# Lcd3_5Connect.net
KiCad netlist of a schematic drawn in EAGLE
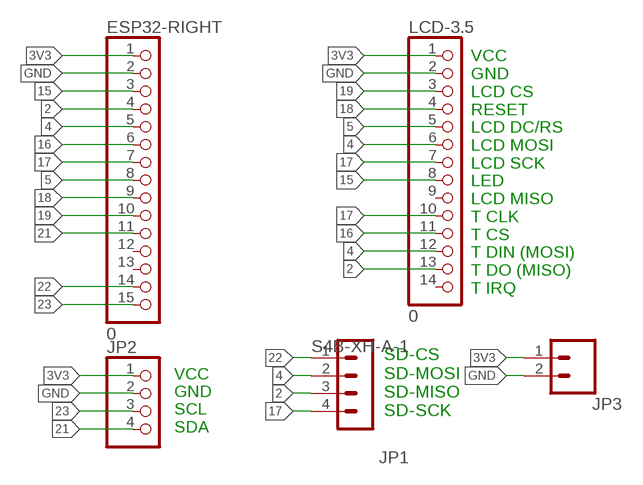
[diagram p0: schematic, sheet 1]

(export (version "E")
  (design (tool "Eeschema 10.0.6"))
  (components
    (comp (ref "ESP32-RIGHT")
      (value "0")
      (footprint "eagle-import:1X15")
      (libsource (lib "eagle-import") (part "PINHD-1X15"))
    )
    (comp (ref "JP1")
      (value "S4B-XH-A-1")
      (footprint "eagle-import:S4B-XH-A-1")
      (libsource (lib "eagle-import") (part "S4B-XH-A-1"))
    )
    (comp (ref "JP2")
      (value "PINHD-1X4")
      (footprint "eagle-import:1X04")
      (libsource (lib "eagle-import") (part "PINHD-1X4"))
    )
    (comp (ref "JP3")
      (value "CONN_02")
      (footprint "eagle-import:1X02")
      (libsource (lib "eagle-import") (part "CONN_02"))
    )
    (comp (ref "LCD-3.5")
      (value "0")
      (footprint "eagle-import:1X14")
      (libsource (lib "eagle-import") (part "PINHD-1X14"))
    )
  )
  (nets
    (net (code "1") (name "2") (class "Default")
      (node (ref "ESP32-RIGHT") (pin "4") (pinfunction "4_4") (pintype "passive"))
      (node (ref "JP1") (pin "3") (pinfunction "3_3") (pintype "passive"))
      (node (ref "LCD-3.5") (pin "13") (pinfunction "13_13") (pintype "passive"))
    )
    (net (code "2") (name "3V3") (class "Default")
      (node (ref "ESP32-RIGHT") (pin "1") (pinfunction "1_1") (pintype "passive"))
      (node (ref "JP2") (pin "1") (pinfunction "1_1") (pintype "passive"))
      (node (ref "JP3") (pin "1") (pinfunction "1_1") (pintype "passive"))
      (node (ref "LCD-3.5") (pin "1") (pinfunction "1_1") (pintype "passive"))
    )
    (net (code "3") (name "4") (class "Default")
      (node (ref "ESP32-RIGHT") (pin "5") (pinfunction "5_5") (pintype "passive"))
      (node (ref "JP1") (pin "2") (pinfunction "2_2") (pintype "passive"))
      (node (ref "LCD-3.5") (pin "12") (pinfunction "12_12") (pintype "passive"))
      (node (ref "LCD-3.5") (pin "6") (pinfunction "6_6") (pintype "passive"))
    )
    (net (code "4") (name "5") (class "Default")
      (node (ref "ESP32-RIGHT") (pin "8") (pinfunction "8_8") (pintype "passive"))
      (node (ref "LCD-3.5") (pin "5") (pinfunction "5_5") (pintype "passive"))
    )
    (net (code "5") (name "15") (class "Default")
      (node (ref "ESP32-RIGHT") (pin "3") (pinfunction "3_3") (pintype "passive"))
      (node (ref "LCD-3.5") (pin "8") (pinfunction "8_8") (pintype "passive"))
    )
    (net (code "6") (name "16") (class "Default")
      (node (ref "ESP32-RIGHT") (pin "6") (pinfunction "6_6") (pintype "passive"))
      (node (ref "LCD-3.5") (pin "11") (pinfunction "11_11") (pintype "passive"))
    )
    (net (code "7") (name "17") (class "Default")
      (node (ref "ESP32-RIGHT") (pin "7") (pinfunction "7_7") (pintype "passive"))
      (node (ref "JP1") (pin "4") (pinfunction "4_4") (pintype "passive"))
      (node (ref "LCD-3.5") (pin "10") (pinfunction "10_10") (pintype "passive"))
      (node (ref "LCD-3.5") (pin "7") (pinfunction "7_7") (pintype "passive"))
    )
    (net (code "8") (name "18") (class "Default")
      (node (ref "ESP32-RIGHT") (pin "9") (pinfunction "9_9") (pintype "passive"))
      (node (ref "LCD-3.5") (pin "4") (pinfunction "4_4") (pintype "passive"))
    )
    (net (code "9") (name "19") (class "Default")
      (node (ref "ESP32-RIGHT") (pin "10") (pinfunction "10_10") (pintype "passive"))
      (node (ref "LCD-3.5") (pin "3") (pinfunction "3_3") (pintype "passive"))
    )
    (net (code "10") (name "21") (class "Default")
      (node (ref "ESP32-RIGHT") (pin "11") (pinfunction "11_11") (pintype "passive"))
      (node (ref "JP2") (pin "4") (pinfunction "4_4") (pintype "passive"))
    )
    (net (code "11") (name "22") (class "Default")
      (node (ref "ESP32-RIGHT") (pin "14") (pinfunction "14_14") (pintype "passive"))
      (node (ref "JP1") (pin "1") (pinfunction "1_1") (pintype "passive"))
    )
    (net (code "12") (name "23") (class "Default")
      (node (ref "ESP32-RIGHT") (pin "15") (pinfunction "15_15") (pintype "passive"))
      (node (ref "JP2") (pin "3") (pinfunction "3_3") (pintype "passive"))
    )
    (net (code "13") (name "GND") (class "Default")
      (node (ref "ESP32-RIGHT") (pin "2") (pinfunction "2_2") (pintype "passive"))
      (node (ref "JP2") (pin "2") (pinfunction "2_2") (pintype "passive"))
      (node (ref "JP3") (pin "2") (pinfunction "2_2") (pintype "passive"))
      (node (ref "LCD-3.5") (pin "2") (pinfunction "2_2") (pintype "passive"))
    )
    (net (code "14") (name "unconnected-(ESP32-RIGHT-Pad12)") (class "Default")
      (node (ref "ESP32-RIGHT") (pin "12") (pinfunction "12_12") (pintype "passive"))
    )
    (net (code "15") (name "unconnected-(ESP32-RIGHT-Pad13)") (class "Default")
      (node (ref "ESP32-RIGHT") (pin "13") (pinfunction "13_13") (pintype "passive"))
    )
    (net (code "16") (name "unconnected-(LCD-3.5-Pad9)") (class "Default")
      (node (ref "LCD-3.5") (pin "9") (pinfunction "9_9") (pintype "passive"))
    )
    (net (code "17") (name "unconnected-(LCD-3.5-Pad14)") (class "Default")
      (node (ref "LCD-3.5") (pin "14") (pinfunction "14_14") (pintype "passive"))
    )
  )
)
